# Analog_isolation.net
KiCad netlist of a schematic drawn in Altium Designer
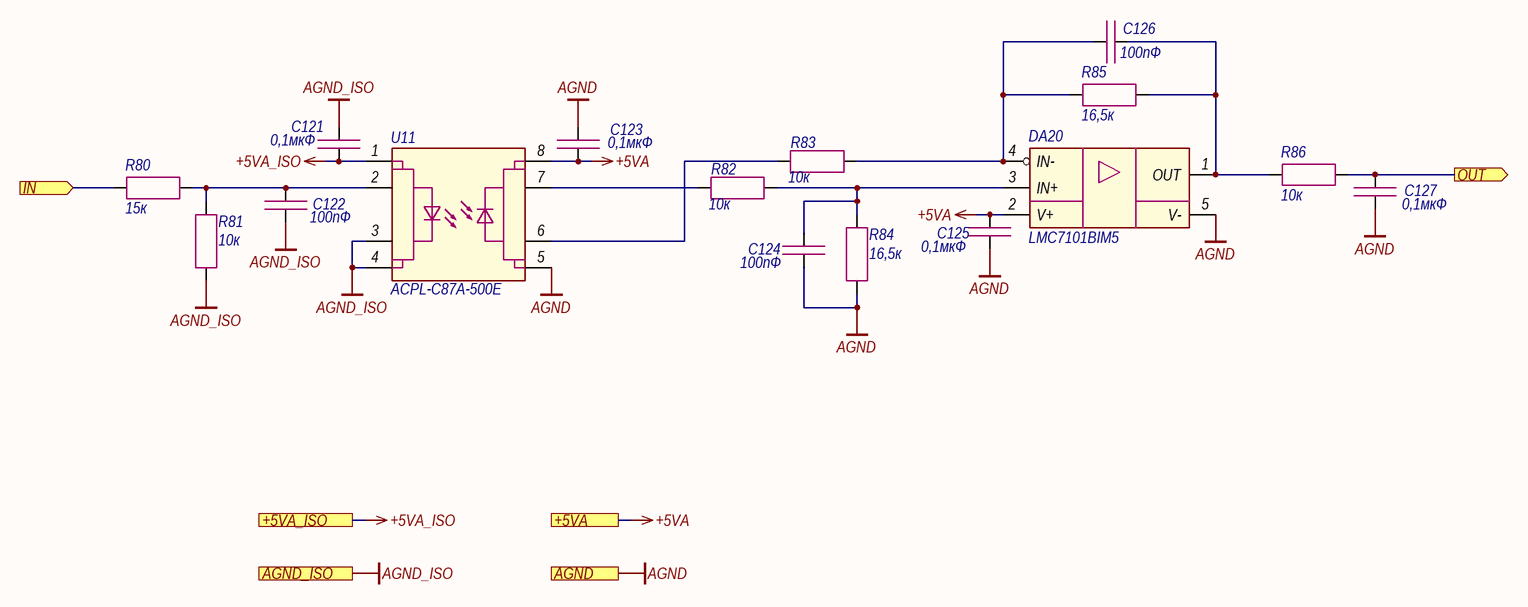
[diagram p0: Analog_isolation.SchDoc]

(export (version "E")
  (design (tool "Eeschema 10.0.6"))
  (components
    (comp (ref "C121")
      (value "0,1мкФ")
      (footprint "Pcb_library:CAP_0603")
      (fields (field (name "MANUFACTURER") "Murata"))
      (libsource (lib "Schem_library") (part "Capacitor"))
    )
    (comp (ref "C122")
      (value "100пФ")
      (footprint "Pcb_library:CAP_0603")
      (fields (field (name "MANUFACTURER") "Murata"))
      (libsource (lib "Schem_library") (part "Capacitor"))
    )
    (comp (ref "C123")
      (value "0,1мкФ")
      (footprint "Pcb_library:CAP_0603")
      (fields (field (name "MANUFACTURER") "Murata"))
      (libsource (lib "Schem_library") (part "Capacitor"))
    )
    (comp (ref "C124")
      (value "100пФ")
      (footprint "Pcb_library:CAP_0603")
      (fields (field (name "MANUFACTURER") "Murata"))
      (libsource (lib "Schem_library") (part "Capacitor"))
    )
    (comp (ref "C125")
      (value "0,1мкФ")
      (footprint "Pcb_library:CAP_0603")
      (fields (field (name "MANUFACTURER") "Murata"))
      (libsource (lib "Schem_library") (part "Capacitor"))
    )
    (comp (ref "C126")
      (value "100пФ")
      (footprint "Pcb_library:CAP_0603")
      (fields (field (name "MANUFACTURER") "Murata"))
      (libsource (lib "Schem_library") (part "Capacitor"))
    )
    (comp (ref "C127")
      (value "0,1мкФ")
      (footprint "Pcb_library:CAP_0603")
      (fields (field (name "MANUFACTURER") "Murata"))
      (libsource (lib "Schem_library") (part "Capacitor"))
    )
    (comp (ref "DA20")
      (value "LMC7101BIM5")
      (footprint "Pcb_library:SOT-23-5")
      (fields (field (name "MANUFACTURER") "Texas Instruments"))
      (libsource (lib "Schem_library") (part "LMC7101"))
    )
    (comp (ref "R80")
      (value "15к")
      (footprint "Pcb_library:RES_0603")
      (fields (field (name "MANUFACTURER") "Yageo"))
      (libsource (lib "Schem_library") (part "Resistor"))
    )
    (comp (ref "R81")
      (value "10к")
      (footprint "Pcb_library:RES_0603")
      (fields (field (name "MANUFACTURER") "Yageo"))
      (libsource (lib "Schem_library") (part "Resistor"))
    )
    (comp (ref "R82")
      (value "10к")
      (footprint "Pcb_library:RES_0603")
      (fields (field (name "MANUFACTURER") "Yageo"))
      (libsource (lib "Schem_library") (part "Resistor"))
    )
    (comp (ref "R83")
      (value "10к")
      (footprint "Pcb_library:RES_0603")
      (fields (field (name "MANUFACTURER") "Yageo"))
      (libsource (lib "Schem_library") (part "Resistor"))
    )
    (comp (ref "R84")
      (value "16,5к")
      (footprint "Pcb_library:RES_0603")
      (fields (field (name "MANUFACTURER") "Yageo"))
      (libsource (lib "Schem_library") (part "Resistor"))
    )
    (comp (ref "R85")
      (value "16,5к")
      (footprint "Pcb_library:RES_0603")
      (fields (field (name "MANUFACTURER") "Yageo"))
      (libsource (lib "Schem_library") (part "Resistor"))
    )
    (comp (ref "R86")
      (value "10к")
      (footprint "Pcb_library:RES_0603")
      (fields (field (name "MANUFACTURER") "Yageo"))
      (libsource (lib "Schem_library") (part "Resistor"))
    )
    (comp (ref "U11")
      (value "ACPL-C87A-500E")
      (footprint "Pcb_library:SSO-8")
      (fields (field (name "MANUFACTURER") "Broadcom"))
      (libsource (lib "Schem_library") (part "ACPL-C87"))
    )
  )
  (nets
    (net (code "1") (name "+5VA") (class "Default")
      (node (ref "C123") (pin "1") (pinfunction "1_1") (pintype "passive"))
      (node (ref "C125") (pin "1") (pinfunction "1_1") (pintype "passive"))
      (node (ref "DA20") (pin "2") (pinfunction "V+_2") (pintype "passive"))
      (node (ref "U11") (pin "8") (pinfunction "VDD2_8") (pintype "passive"))
    )
    (net (code "2") (name "+5VA_ISO") (class "Default")
      (node (ref "C121") (pin "1") (pinfunction "1_1") (pintype "passive"))
      (node (ref "U11") (pin "1") (pinfunction "VDD1_1") (pintype "passive"))
    )
    (net (code "3") (name "/IN") (class "Default")
      (node (ref "R80") (pin "2") (pinfunction "2_2") (pintype "passive"))
    )
    (net (code "4") (name "/OUT") (class "Default")
      (node (ref "C127") (pin "1") (pinfunction "1_1") (pintype "passive"))
      (node (ref "R86") (pin "2") (pinfunction "2_2") (pintype "passive"))
    )
    (net (code "5") (name "AGND") (class "Default")
      (node (ref "C123") (pin "2") (pinfunction "2_2") (pintype "passive"))
      (node (ref "C124") (pin "2") (pinfunction "2_2") (pintype "passive"))
      (node (ref "C125") (pin "2") (pinfunction "2_2") (pintype "passive"))
      (node (ref "C127") (pin "2") (pinfunction "2_2") (pintype "passive"))
      (node (ref "DA20") (pin "5") (pinfunction "V-_5") (pintype "passive"))
      (node (ref "R84") (pin "2") (pinfunction "2_2") (pintype "passive"))
      (node (ref "U11") (pin "5") (pinfunction "GND2_5") (pintype "passive"))
    )
    (net (code "6") (name "AGND_ISO") (class "Default")
      (node (ref "C121") (pin "2") (pinfunction "2_2") (pintype "passive"))
      (node (ref "C122") (pin "1") (pinfunction "1_1") (pintype "passive"))
      (node (ref "R81") (pin "2") (pinfunction "2_2") (pintype "passive"))
      (node (ref "U11") (pin "3") (pinfunction "SHDN_3") (pintype "passive"))
      (node (ref "U11") (pin "4") (pinfunction "GND1_4") (pintype "passive"))
    )
    (net (code "7") (name "Net-(DA20-IN+)") (class "Default")
      (node (ref "C124") (pin "1") (pinfunction "1_1") (pintype "passive"))
      (node (ref "DA20") (pin "3") (pinfunction "IN+_3") (pintype "passive"))
      (node (ref "R82") (pin "2") (pinfunction "2_2") (pintype "passive"))
      (node (ref "R84") (pin "1") (pinfunction "1_1") (pintype "passive"))
    )
    (net (code "8") (name "Net-(DA20-IN-)") (class "Default")
      (node (ref "C126") (pin "1") (pinfunction "1_1") (pintype "passive"))
      (node (ref "DA20") (pin "4") (pinfunction "IN-_4") (pintype "passive"))
      (node (ref "R83") (pin "2") (pinfunction "2_2") (pintype "passive"))
      (node (ref "R85") (pin "2") (pinfunction "2_2") (pintype "passive"))
    )
    (net (code "9") (name "Net-(DA20-OUT)") (class "Default")
      (node (ref "C126") (pin "2") (pinfunction "2_2") (pintype "passive"))
      (node (ref "DA20") (pin "1") (pinfunction "OUT_1") (pintype "passive"))
      (node (ref "R85") (pin "1") (pinfunction "1_1") (pintype "passive"))
      (node (ref "R86") (pin "1") (pinfunction "1_1") (pintype "passive"))
    )
    (net (code "10") (name "Net-(U11-VIN)") (class "Default")
      (node (ref "C122") (pin "2") (pinfunction "2_2") (pintype "passive"))
      (node (ref "R80") (pin "1") (pinfunction "1_1") (pintype "passive"))
      (node (ref "R81") (pin "1") (pinfunction "1_1") (pintype "passive"))
      (node (ref "U11") (pin "2") (pinfunction "VIN_2") (pintype "passive"))
    )
    (net (code "11") (name "Net-(U11-VOUT+)") (class "Default")
      (node (ref "R82") (pin "1") (pinfunction "1_1") (pintype "passive"))
      (node (ref "U11") (pin "7") (pinfunction "VOUT+_7") (pintype "passive"))
    )
    (net (code "12") (name "Net-(U11-VOUT-)") (class "Default")
      (node (ref "R83") (pin "1") (pinfunction "1_1") (pintype "passive"))
      (node (ref "U11") (pin "6") (pinfunction "VOUT-_6") (pintype "passive"))
    )
  )
)
